# minimal_kl05z.net
KiCad netlist of a schematic drawn in EAGLE
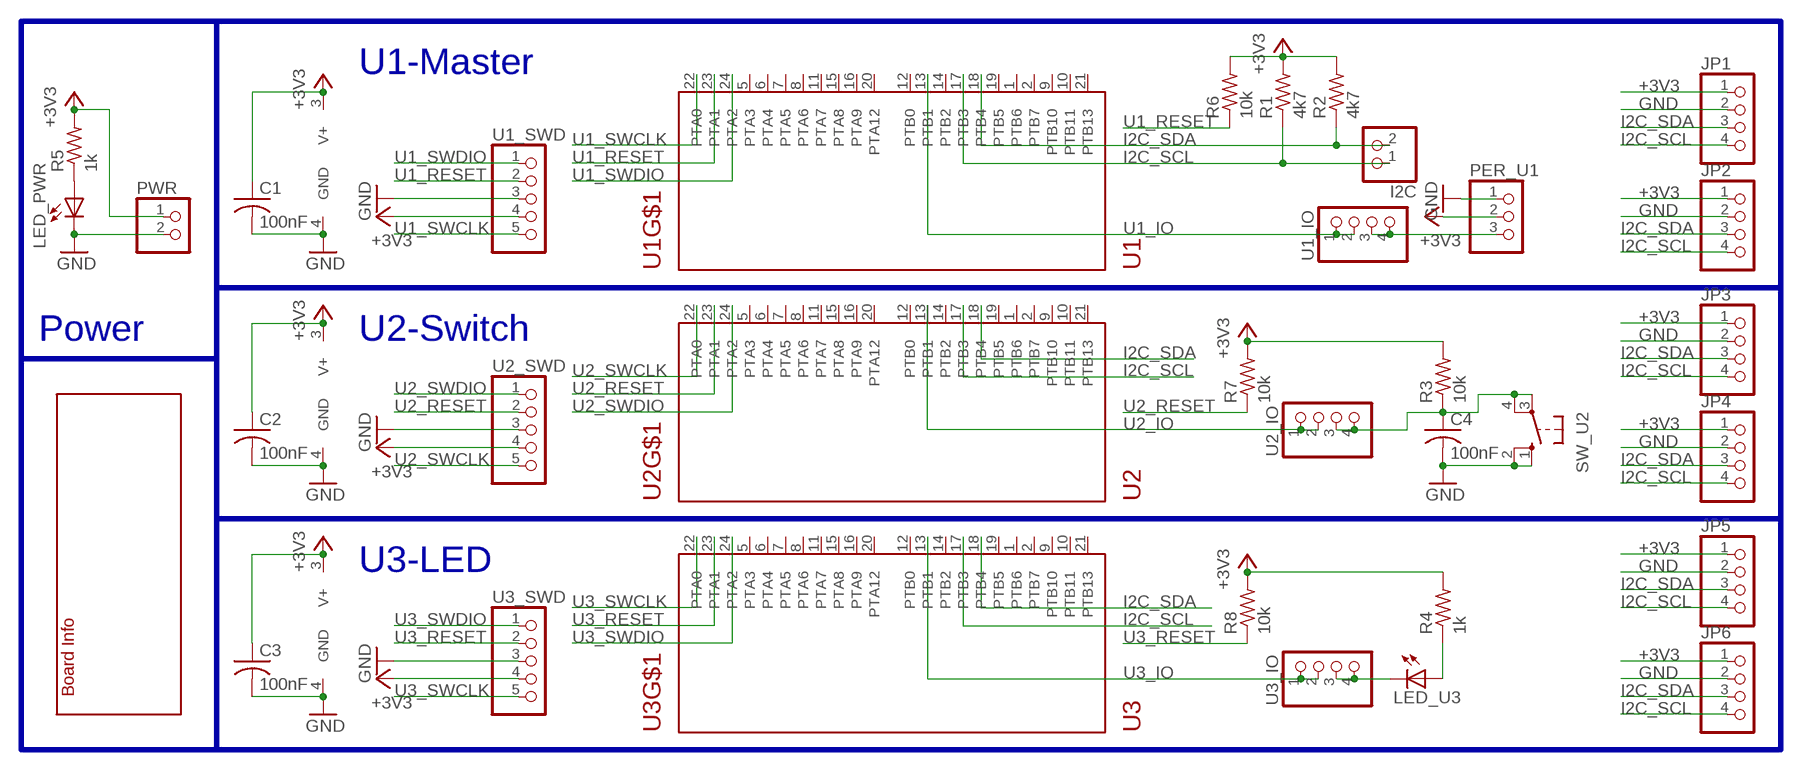
[diagram p0: schematic, sheet 1]

(export (version "E")
  (design (tool "Eeschema 10.0.6"))
  (components
    (comp (ref "C1")
      (value "100nF")
      (footprint "eagle-import:C025-025X050")
      (libsource (lib "eagle-import") (part "C-US025-025X050"))
    )
    (comp (ref "C2")
      (value "100nF")
      (footprint "eagle-import:C025-025X050")
      (libsource (lib "eagle-import") (part "C-US025-025X050"))
    )
    (comp (ref "C3")
      (value "100nF")
      (footprint "eagle-import:C025-025X050")
      (libsource (lib "eagle-import") (part "C-US025-025X050"))
    )
    (comp (ref "C4")
      (value "100nF")
      (footprint "eagle-import:C025-025X050")
      (libsource (lib "eagle-import") (part "C-US025-025X050"))
    )
    (comp (ref "I2C")
      (value "PINHD-1X2")
      (footprint "eagle-import:1X02")
      (libsource (lib "eagle-import") (part "PINHD-1X2"))
    )
    (comp (ref "JP1")
      (value "PINHD-1X4")
      (footprint "eagle-import:1X04")
      (libsource (lib "eagle-import") (part "PINHD-1X4"))
    )
    (comp (ref "JP2")
      (value "PINHD-1X4")
      (footprint "eagle-import:1X04")
      (libsource (lib "eagle-import") (part "PINHD-1X4"))
    )
    (comp (ref "JP3")
      (value "PINHD-1X4")
      (footprint "eagle-import:1X04")
      (libsource (lib "eagle-import") (part "PINHD-1X4"))
    )
    (comp (ref "JP4")
      (value "PINHD-1X4")
      (footprint "eagle-import:1X04")
      (libsource (lib "eagle-import") (part "PINHD-1X4"))
    )
    (comp (ref "JP5")
      (value "PINHD-1X4")
      (footprint "eagle-import:1X04")
      (libsource (lib "eagle-import") (part "PINHD-1X4"))
    )
    (comp (ref "JP6")
      (value "PINHD-1X4")
      (footprint "eagle-import:1X04")
      (libsource (lib "eagle-import") (part "PINHD-1X4"))
    )
    (comp (ref "LED_PWR")
      (value "LED5MM")
      (footprint "eagle-import:LED5MM")
      (libsource (lib "eagle-import") (part "LED5MM"))
    )
    (comp (ref "LED_U3")
      (value "LED5MM")
      (footprint "eagle-import:LED5MM")
      (libsource (lib "eagle-import") (part "LED5MM"))
    )
    (comp (ref "PER_U1")
      (value "PINHD-1X3")
      (footprint "eagle-import:1X03")
      (libsource (lib "eagle-import") (part "PINHD-1X3"))
    )
    (comp (ref "PWR")
      (value "PINHD-1X2")
      (footprint "eagle-import:1X02")
      (libsource (lib "eagle-import") (part "PINHD-1X2"))
    )
    (comp (ref "R1")
      (value "4k7")
      (footprint "eagle-import:0204_7")
      (libsource (lib "eagle-import") (part "R-US_0204/7"))
    )
    (comp (ref "R2")
      (value "4k7")
      (footprint "eagle-import:0204_7")
      (libsource (lib "eagle-import") (part "R-US_0204/7"))
    )
    (comp (ref "R3")
      (value "10k")
      (footprint "eagle-import:0204V")
      (libsource (lib "eagle-import") (part "R-US_0204/2V"))
    )
    (comp (ref "R4")
      (value "1k")
      (footprint "eagle-import:0204V")
      (libsource (lib "eagle-import") (part "R-US_0204/2V"))
    )
    (comp (ref "R5")
      (value "1k")
      (footprint "eagle-import:0204V")
      (libsource (lib "eagle-import") (part "R-US_0204/2V"))
    )
    (comp (ref "R6")
      (value "10k")
      (footprint "eagle-import:0204_7")
      (libsource (lib "eagle-import") (part "R-US_0204/7"))
    )
    (comp (ref "R7")
      (value "10k")
      (footprint "eagle-import:0204_7")
      (libsource (lib "eagle-import") (part "R-US_0204/7"))
    )
    (comp (ref "R8")
      (value "10k")
      (footprint "eagle-import:0204_7")
      (libsource (lib "eagle-import") (part "R-US_0204/7"))
    )
    (comp (ref "SW_U2")
      (value "10-XX")
      (footprint "eagle-import:B3F-10XX")
      (fields (field (name "MPN") "B3F-1000"))
      (libsource (lib "eagle-import") (part "10-XX"))
    )
    (comp (ref "U$1")
      (value "INFO")
      (footprint "eagle-import:INFO")
      (fields
        (field (name "AUTHOR") "Austin Buchan")
        (field (name "DATE") "Jul 7, 2015")
        (field (name "DESIGN") "MinimalKL05Z")
        (field (name "ORGANIZATION") "UC Berkeley ASPIRE")
        (field (name "REVISION") "r0.0")
      )
      (libsource (lib "eagle-import") (part "INFO"))
    )
    (comp (ref "U1")
      (value "MKL05Z32VFK4-DIP")
      (footprint "eagle-import:DIL24-3")
      (libsource (lib "eagle-import") (part "MKL05Z32VFK4-DIP"))
    )
    (comp (ref "U1_IO")
      (value "PINHD-1X4")
      (footprint "eagle-import:1X04")
      (libsource (lib "eagle-import") (part "PINHD-1X4"))
    )
    (comp (ref "U1_SWD")
      (value "PINHD-1X5")
      (footprint "eagle-import:1X05")
      (libsource (lib "eagle-import") (part "PINHD-1X5"))
    )
    (comp (ref "U2")
      (value "MKL05Z32VFK4-DIP")
      (footprint "eagle-import:DIL24-3")
      (libsource (lib "eagle-import") (part "MKL05Z32VFK4-DIP"))
    )
    (comp (ref "U2_IO")
      (value "PINHD-1X4")
      (footprint "eagle-import:1X04")
      (libsource (lib "eagle-import") (part "PINHD-1X4"))
    )
    (comp (ref "U2_SWD")
      (value "PINHD-1X5")
      (footprint "eagle-import:1X05")
      (libsource (lib "eagle-import") (part "PINHD-1X5"))
    )
    (comp (ref "U3")
      (value "MKL05Z32VFK4-DIP")
      (footprint "eagle-import:DIL24-3")
      (libsource (lib "eagle-import") (part "MKL05Z32VFK4-DIP"))
    )
    (comp (ref "U3_IO")
      (value "PINHD-1X4")
      (footprint "eagle-import:1X04")
      (libsource (lib "eagle-import") (part "PINHD-1X4"))
    )
    (comp (ref "U3_SWD")
      (value "PINHD-1X5")
      (footprint "eagle-import:1X05")
      (libsource (lib "eagle-import") (part "PINHD-1X5"))
    )
  )
  (nets
    (net (code "1") (name "+3V3") (class "Default")
      (node (ref "C1") (pin "1") (pinfunction "1_1") (pintype "passive"))
      (node (ref "C2") (pin "1") (pinfunction "1_1") (pintype "passive"))
      (node (ref "C3") (pin "1") (pinfunction "1_1") (pintype "passive"))
      (node (ref "JP1") (pin "1") (pinfunction "1_1") (pintype "passive"))
      (node (ref "JP2") (pin "1") (pinfunction "1_1") (pintype "passive"))
      (node (ref "JP3") (pin "1") (pinfunction "1_1") (pintype "passive"))
      (node (ref "JP4") (pin "1") (pinfunction "1_1") (pintype "passive"))
      (node (ref "JP5") (pin "1") (pinfunction "1_1") (pintype "passive"))
      (node (ref "JP6") (pin "1") (pinfunction "1_1") (pintype "passive"))
      (node (ref "PER_U1") (pin "2") (pinfunction "2_2") (pintype "passive"))
      (node (ref "PWR") (pin "1") (pinfunction "1_1") (pintype "passive"))
      (node (ref "R1") (pin "2") (pinfunction "2_2") (pintype "passive"))
      (node (ref "R2") (pin "2") (pinfunction "2_2") (pintype "passive"))
      (node (ref "R3") (pin "2") (pinfunction "2_2") (pintype "passive"))
      (node (ref "R4") (pin "2") (pinfunction "2_2") (pintype "passive"))
      (node (ref "R5") (pin "2") (pinfunction "2_2") (pintype "passive"))
      (node (ref "R6") (pin "2") (pinfunction "2_2") (pintype "passive"))
      (node (ref "R7") (pin "2") (pinfunction "2_2") (pintype "passive"))
      (node (ref "R8") (pin "2") (pinfunction "2_2") (pintype "passive"))
      (node (ref "U1") (pin "3") (pinfunction "V+_3") (pintype "power_in"))
      (node (ref "U1_SWD") (pin "4") (pinfunction "4_4") (pintype "passive"))
      (node (ref "U2") (pin "3") (pinfunction "V+_3") (pintype "power_in"))
      (node (ref "U2_SWD") (pin "4") (pinfunction "4_4") (pintype "passive"))
      (node (ref "U3") (pin "3") (pinfunction "V+_3") (pintype "power_in"))
      (node (ref "U3_SWD") (pin "4") (pinfunction "4_4") (pintype "passive"))
    )
    (net (code "2") (name "/I2C_SCL") (class "Default")
      (node (ref "I2C") (pin "1") (pinfunction "1_1") (pintype "passive"))
      (node (ref "JP1") (pin "4") (pinfunction "4_4") (pintype "passive"))
      (node (ref "JP2") (pin "4") (pinfunction "4_4") (pintype "passive"))
      (node (ref "JP3") (pin "4") (pinfunction "4_4") (pintype "passive"))
      (node (ref "JP4") (pin "4") (pinfunction "4_4") (pintype "passive"))
      (node (ref "JP5") (pin "4") (pinfunction "4_4") (pintype "passive"))
      (node (ref "JP6") (pin "4") (pinfunction "4_4") (pintype "passive"))
      (node (ref "R1") (pin "1") (pinfunction "1_1") (pintype "passive"))
      (node (ref "U1") (pin "17") (pinfunction "PTB3_17") (pintype "bidirectional"))
      (node (ref "U2") (pin "17") (pinfunction "PTB3_17") (pintype "bidirectional"))
      (node (ref "U3") (pin "17") (pinfunction "PTB3_17") (pintype "bidirectional"))
    )
    (net (code "3") (name "/I2C_SDA") (class "Default")
      (node (ref "I2C") (pin "2") (pinfunction "2_2") (pintype "passive"))
      (node (ref "JP1") (pin "3") (pinfunction "3_3") (pintype "passive"))
      (node (ref "JP2") (pin "3") (pinfunction "3_3") (pintype "passive"))
      (node (ref "JP3") (pin "3") (pinfunction "3_3") (pintype "passive"))
      (node (ref "JP4") (pin "3") (pinfunction "3_3") (pintype "passive"))
      (node (ref "JP5") (pin "3") (pinfunction "3_3") (pintype "passive"))
      (node (ref "JP6") (pin "3") (pinfunction "3_3") (pintype "passive"))
      (node (ref "R2") (pin "1") (pinfunction "1_1") (pintype "passive"))
      (node (ref "U1") (pin "18") (pinfunction "PTB4_18") (pintype "bidirectional"))
      (node (ref "U2") (pin "18") (pinfunction "PTB4_18") (pintype "bidirectional"))
      (node (ref "U3") (pin "18") (pinfunction "PTB4_18") (pintype "bidirectional"))
    )
    (net (code "4") (name "/U1_IO") (class "Default")
      (node (ref "U1") (pin "13") (pinfunction "PTB1_13") (pintype "bidirectional"))
      (node (ref "U1_IO") (pin "1") (pinfunction "1_1") (pintype "passive"))
      (node (ref "U1_IO") (pin "2") (pinfunction "2_2") (pintype "passive"))
    )
    (net (code "5") (name "/U1_RESET") (class "Default")
      (node (ref "R6") (pin "1") (pinfunction "1_1") (pintype "passive"))
      (node (ref "U1") (pin "23") (pinfunction "PTA1_23") (pintype "bidirectional"))
      (node (ref "U1_SWD") (pin "2") (pinfunction "2_2") (pintype "passive"))
    )
    (net (code "6") (name "/U1_SWCLK") (class "Default")
      (node (ref "U1") (pin "22") (pinfunction "PTA0_22") (pintype "bidirectional"))
      (node (ref "U1_SWD") (pin "5") (pinfunction "5_5") (pintype "passive"))
    )
    (net (code "7") (name "/U1_SWDIO") (class "Default")
      (node (ref "U1") (pin "24") (pinfunction "PTA2_24") (pintype "bidirectional"))
      (node (ref "U1_SWD") (pin "1") (pinfunction "1_1") (pintype "passive"))
    )
    (net (code "8") (name "/U2_IO") (class "Default")
      (node (ref "U2") (pin "13") (pinfunction "PTB1_13") (pintype "bidirectional"))
      (node (ref "U2_IO") (pin "1") (pinfunction "1_1") (pintype "passive"))
      (node (ref "U2_IO") (pin "2") (pinfunction "2_2") (pintype "passive"))
    )
    (net (code "9") (name "/U2_RESET") (class "Default")
      (node (ref "R7") (pin "1") (pinfunction "1_1") (pintype "passive"))
      (node (ref "U2") (pin "23") (pinfunction "PTA1_23") (pintype "bidirectional"))
      (node (ref "U2_SWD") (pin "2") (pinfunction "2_2") (pintype "passive"))
    )
    (net (code "10") (name "/U2_SWCLK") (class "Default")
      (node (ref "U2") (pin "22") (pinfunction "PTA0_22") (pintype "bidirectional"))
      (node (ref "U2_SWD") (pin "5") (pinfunction "5_5") (pintype "passive"))
    )
    (net (code "11") (name "/U2_SWDIO") (class "Default")
      (node (ref "U2") (pin "24") (pinfunction "PTA2_24") (pintype "bidirectional"))
      (node (ref "U2_SWD") (pin "1") (pinfunction "1_1") (pintype "passive"))
    )
    (net (code "12") (name "/U3_IO") (class "Default")
      (node (ref "U3") (pin "13") (pinfunction "PTB1_13") (pintype "bidirectional"))
      (node (ref "U3_IO") (pin "1") (pinfunction "1_1") (pintype "passive"))
      (node (ref "U3_IO") (pin "2") (pinfunction "2_2") (pintype "passive"))
    )
    (net (code "13") (name "/U3_RESET") (class "Default")
      (node (ref "R8") (pin "1") (pinfunction "1_1") (pintype "passive"))
      (node (ref "U3") (pin "23") (pinfunction "PTA1_23") (pintype "bidirectional"))
      (node (ref "U3_SWD") (pin "2") (pinfunction "2_2") (pintype "passive"))
    )
    (net (code "14") (name "/U3_SWCLK") (class "Default")
      (node (ref "U3") (pin "22") (pinfunction "PTA0_22") (pintype "bidirectional"))
      (node (ref "U3_SWD") (pin "5") (pinfunction "5_5") (pintype "passive"))
    )
    (net (code "15") (name "/U3_SWDIO") (class "Default")
      (node (ref "U3") (pin "24") (pinfunction "PTA2_24") (pintype "bidirectional"))
      (node (ref "U3_SWD") (pin "1") (pinfunction "1_1") (pintype "passive"))
    )
    (net (code "16") (name "GND") (class "Default")
      (node (ref "C1") (pin "2") (pinfunction "2_2") (pintype "passive"))
      (node (ref "C2") (pin "2") (pinfunction "2_2") (pintype "passive"))
      (node (ref "C3") (pin "2") (pinfunction "2_2") (pintype "passive"))
      (node (ref "C4") (pin "2") (pinfunction "2_2") (pintype "passive"))
      (node (ref "JP1") (pin "2") (pinfunction "2_2") (pintype "passive"))
      (node (ref "JP2") (pin "2") (pinfunction "2_2") (pintype "passive"))
      (node (ref "JP3") (pin "2") (pinfunction "2_2") (pintype "passive"))
      (node (ref "JP4") (pin "2") (pinfunction "2_2") (pintype "passive"))
      (node (ref "JP5") (pin "2") (pinfunction "2_2") (pintype "passive"))
      (node (ref "JP6") (pin "2") (pinfunction "2_2") (pintype "passive"))
      (node (ref "LED_PWR") (pin "K") (pinfunction "C_K") (pintype "passive"))
      (node (ref "PER_U1") (pin "1") (pinfunction "1_1") (pintype "passive"))
      (node (ref "PWR") (pin "2") (pinfunction "2_2") (pintype "passive"))
      (node (ref "SW_U2") (pin "1") (pinfunction "S_1") (pintype "passive"))
      (node (ref "SW_U2") (pin "2") (pinfunction "S1_2") (pintype "passive"))
      (node (ref "U1") (pin "4") (pinfunction "GND_4") (pintype "power_in"))
      (node (ref "U1_SWD") (pin "3") (pinfunction "3_3") (pintype "passive"))
      (node (ref "U2") (pin "4") (pinfunction "GND_4") (pintype "power_in"))
      (node (ref "U2_SWD") (pin "3") (pinfunction "3_3") (pintype "passive"))
      (node (ref "U3") (pin "4") (pinfunction "GND_4") (pintype "power_in"))
      (node (ref "U3_SWD") (pin "3") (pinfunction "3_3") (pintype "passive"))
    )
    (net (code "17") (name "Net-(LED_PWR-PadA)") (class "Default")
      (node (ref "LED_PWR") (pin "A") (pinfunction "A_A") (pintype "passive"))
      (node (ref "R5") (pin "1") (pinfunction "1_1") (pintype "passive"))
    )
    (net (code "18") (name "Net-(LED_U3-C)") (class "Default")
      (node (ref "LED_U3") (pin "K") (pinfunction "C_K") (pintype "passive"))
      (node (ref "U3_IO") (pin "3") (pinfunction "3_3") (pintype "passive"))
      (node (ref "U3_IO") (pin "4") (pinfunction "4_4") (pintype "passive"))
    )
    (net (code "19") (name "Net-(LED_U3-PadA)") (class "Default")
      (node (ref "LED_U3") (pin "A") (pinfunction "A_A") (pintype "passive"))
      (node (ref "R4") (pin "1") (pinfunction "1_1") (pintype "passive"))
    )
    (net (code "20") (name "Net-(PER_U1-Pad3)") (class "Default")
      (node (ref "PER_U1") (pin "3") (pinfunction "3_3") (pintype "passive"))
      (node (ref "U1_IO") (pin "3") (pinfunction "3_3") (pintype "passive"))
      (node (ref "U1_IO") (pin "4") (pinfunction "4_4") (pintype "passive"))
    )
    (net (code "21") (name "Net-(SW_U2-P)") (class "Default")
      (node (ref "C4") (pin "1") (pinfunction "1_1") (pintype "passive"))
      (node (ref "R3") (pin "1") (pinfunction "1_1") (pintype "passive"))
      (node (ref "SW_U2") (pin "3") (pinfunction "P_3") (pintype "passive"))
      (node (ref "SW_U2") (pin "4") (pinfunction "P1_4") (pintype "passive"))
      (node (ref "U2_IO") (pin "3") (pinfunction "3_3") (pintype "passive"))
      (node (ref "U2_IO") (pin "4") (pinfunction "4_4") (pintype "passive"))
    )
    (net (code "22") (name "unconnected-(U1A-PTA3-Pad5)") (class "Default")
      (node (ref "U1") (pin "5") (pinfunction "PTA3_5") (pintype "bidirectional"))
    )
    (net (code "23") (name "unconnected-(U1A-PTA4-Pad6)") (class "Default")
      (node (ref "U1") (pin "6") (pinfunction "PTA4_6") (pintype "bidirectional"))
    )
    (net (code "24") (name "unconnected-(U1A-PTA5-Pad7)") (class "Default")
      (node (ref "U1") (pin "7") (pinfunction "PTA5_7") (pintype "bidirectional"))
    )
    (net (code "25") (name "unconnected-(U1A-PTA6-Pad8)") (class "Default")
      (node (ref "U1") (pin "8") (pinfunction "PTA6_8") (pintype "bidirectional"))
    )
    (net (code "26") (name "unconnected-(U1A-PTA7-Pad11)") (class "Default")
      (node (ref "U1") (pin "11") (pinfunction "PTA7_11") (pintype "bidirectional"))
    )
    (net (code "27") (name "unconnected-(U1A-PTA8-Pad15)") (class "Default")
      (node (ref "U1") (pin "15") (pinfunction "PTA8_15") (pintype "bidirectional"))
    )
    (net (code "28") (name "unconnected-(U1A-PTA9-Pad16)") (class "Default")
      (node (ref "U1") (pin "16") (pinfunction "PTA9_16") (pintype "bidirectional"))
    )
    (net (code "29") (name "unconnected-(U1A-PTA12-Pad20)") (class "Default")
      (node (ref "U1") (pin "20") (pinfunction "PTA12_20") (pintype "bidirectional"))
    )
    (net (code "30") (name "unconnected-(U1A-PTB0-Pad12)") (class "Default")
      (node (ref "U1") (pin "12") (pinfunction "PTB0_12") (pintype "bidirectional"))
    )
    (net (code "31") (name "unconnected-(U1A-PTB2-Pad14)") (class "Default")
      (node (ref "U1") (pin "14") (pinfunction "PTB2_14") (pintype "bidirectional"))
    )
    (net (code "32") (name "unconnected-(U1A-PTB5-Pad19)") (class "Default")
      (node (ref "U1") (pin "19") (pinfunction "PTB5_19") (pintype "bidirectional"))
    )
    (net (code "33") (name "unconnected-(U1A-PTB6-Pad1)") (class "Default")
      (node (ref "U1") (pin "1") (pinfunction "PTB6_1") (pintype "bidirectional"))
    )
    (net (code "34") (name "unconnected-(U1A-PTB7-Pad2)") (class "Default")
      (node (ref "U1") (pin "2") (pinfunction "PTB7_2") (pintype "bidirectional"))
    )
    (net (code "35") (name "unconnected-(U1A-PTB10-Pad9)") (class "Default")
      (node (ref "U1") (pin "9") (pinfunction "PTB10_9") (pintype "bidirectional"))
    )
    (net (code "36") (name "unconnected-(U1A-PTB11-Pad10)") (class "Default")
      (node (ref "U1") (pin "10") (pinfunction "PTB11_10") (pintype "bidirectional"))
    )
    (net (code "37") (name "unconnected-(U1A-PTB13-Pad21)") (class "Default")
      (node (ref "U1") (pin "21") (pinfunction "PTB13_21") (pintype "bidirectional"))
    )
    (net (code "38") (name "unconnected-(U2A-PTA3-Pad5)") (class "Default")
      (node (ref "U2") (pin "5") (pinfunction "PTA3_5") (pintype "bidirectional"))
    )
    (net (code "39") (name "unconnected-(U2A-PTA4-Pad6)") (class "Default")
      (node (ref "U2") (pin "6") (pinfunction "PTA4_6") (pintype "bidirectional"))
    )
    (net (code "40") (name "unconnected-(U2A-PTA5-Pad7)") (class "Default")
      (node (ref "U2") (pin "7") (pinfunction "PTA5_7") (pintype "bidirectional"))
    )
    (net (code "41") (name "unconnected-(U2A-PTA6-Pad8)") (class "Default")
      (node (ref "U2") (pin "8") (pinfunction "PTA6_8") (pintype "bidirectional"))
    )
    (net (code "42") (name "unconnected-(U2A-PTA7-Pad11)") (class "Default")
      (node (ref "U2") (pin "11") (pinfunction "PTA7_11") (pintype "bidirectional"))
    )
    (net (code "43") (name "unconnected-(U2A-PTA8-Pad15)") (class "Default")
      (node (ref "U2") (pin "15") (pinfunction "PTA8_15") (pintype "bidirectional"))
    )
    (net (code "44") (name "unconnected-(U2A-PTA9-Pad16)") (class "Default")
      (node (ref "U2") (pin "16") (pinfunction "PTA9_16") (pintype "bidirectional"))
    )
    (net (code "45") (name "unconnected-(U2A-PTA12-Pad20)") (class "Default")
      (node (ref "U2") (pin "20") (pinfunction "PTA12_20") (pintype "bidirectional"))
    )
    (net (code "46") (name "unconnected-(U2A-PTB0-Pad12)") (class "Default")
      (node (ref "U2") (pin "12") (pinfunction "PTB0_12") (pintype "bidirectional"))
    )
    (net (code "47") (name "unconnected-(U2A-PTB2-Pad14)") (class "Default")
      (node (ref "U2") (pin "14") (pinfunction "PTB2_14") (pintype "bidirectional"))
    )
    (net (code "48") (name "unconnected-(U2A-PTB5-Pad19)") (class "Default")
      (node (ref "U2") (pin "19") (pinfunction "PTB5_19") (pintype "bidirectional"))
    )
    (net (code "49") (name "unconnected-(U2A-PTB6-Pad1)") (class "Default")
      (node (ref "U2") (pin "1") (pinfunction "PTB6_1") (pintype "bidirectional"))
    )
    (net (code "50") (name "unconnected-(U2A-PTB7-Pad2)") (class "Default")
      (node (ref "U2") (pin "2") (pinfunction "PTB7_2") (pintype "bidirectional"))
    )
    (net (code "51") (name "unconnected-(U2A-PTB10-Pad9)") (class "Default")
      (node (ref "U2") (pin "9") (pinfunction "PTB10_9") (pintype "bidirectional"))
    )
    (net (code "52") (name "unconnected-(U2A-PTB11-Pad10)") (class "Default")
      (node (ref "U2") (pin "10") (pinfunction "PTB11_10") (pintype "bidirectional"))
    )
    (net (code "53") (name "unconnected-(U2A-PTB13-Pad21)") (class "Default")
      (node (ref "U2") (pin "21") (pinfunction "PTB13_21") (pintype "bidirectional"))
    )
    (net (code "54") (name "unconnected-(U3A-PTA3-Pad5)") (class "Default")
      (node (ref "U3") (pin "5") (pinfunction "PTA3_5") (pintype "bidirectional"))
    )
    (net (code "55") (name "unconnected-(U3A-PTA4-Pad6)") (class "Default")
      (node (ref "U3") (pin "6") (pinfunction "PTA4_6") (pintype "bidirectional"))
    )
    (net (code "56") (name "unconnected-(U3A-PTA5-Pad7)") (class "Default")
      (node (ref "U3") (pin "7") (pinfunction "PTA5_7") (pintype "bidirectional"))
    )
    (net (code "57") (name "unconnected-(U3A-PTA6-Pad8)") (class "Default")
      (node (ref "U3") (pin "8") (pinfunction "PTA6_8") (pintype "bidirectional"))
    )
    (net (code "58") (name "unconnected-(U3A-PTA7-Pad11)") (class "Default")
      (node (ref "U3") (pin "11") (pinfunction "PTA7_11") (pintype "bidirectional"))
    )
    (net (code "59") (name "unconnected-(U3A-PTA8-Pad15)") (class "Default")
      (node (ref "U3") (pin "15") (pinfunction "PTA8_15") (pintype "bidirectional"))
    )
    (net (code "60") (name "unconnected-(U3A-PTA9-Pad16)") (class "Default")
      (node (ref "U3") (pin "16") (pinfunction "PTA9_16") (pintype "bidirectional"))
    )
    (net (code "61") (name "unconnected-(U3A-PTA12-Pad20)") (class "Default")
      (node (ref "U3") (pin "20") (pinfunction "PTA12_20") (pintype "bidirectional"))
    )
    (net (code "62") (name "unconnected-(U3A-PTB0-Pad12)") (class "Default")
      (node (ref "U3") (pin "12") (pinfunction "PTB0_12") (pintype "bidirectional"))
    )
    (net (code "63") (name "unconnected-(U3A-PTB2-Pad14)") (class "Default")
      (node (ref "U3") (pin "14") (pinfunction "PTB2_14") (pintype "bidirectional"))
    )
    (net (code "64") (name "unconnected-(U3A-PTB5-Pad19)") (class "Default")
      (node (ref "U3") (pin "19") (pinfunction "PTB5_19") (pintype "bidirectional"))
    )
    (net (code "65") (name "unconnected-(U3A-PTB6-Pad1)") (class "Default")
      (node (ref "U3") (pin "1") (pinfunction "PTB6_1") (pintype "bidirectional"))
    )
    (net (code "66") (name "unconnected-(U3A-PTB7-Pad2)") (class "Default")
      (node (ref "U3") (pin "2") (pinfunction "PTB7_2") (pintype "bidirectional"))
    )
    (net (code "67") (name "unconnected-(U3A-PTB10-Pad9)") (class "Default")
      (node (ref "U3") (pin "9") (pinfunction "PTB10_9") (pintype "bidirectional"))
    )
    (net (code "68") (name "unconnected-(U3A-PTB11-Pad10)") (class "Default")
      (node (ref "U3") (pin "10") (pinfunction "PTB11_10") (pintype "bidirectional"))
    )
    (net (code "69") (name "unconnected-(U3A-PTB13-Pad21)") (class "Default")
      (node (ref "U3") (pin "21") (pinfunction "PTB13_21") (pintype "bidirectional"))
    )
  )
)
